# furby_board_v1.net
KiCad netlist of a schematic drawn in EAGLE
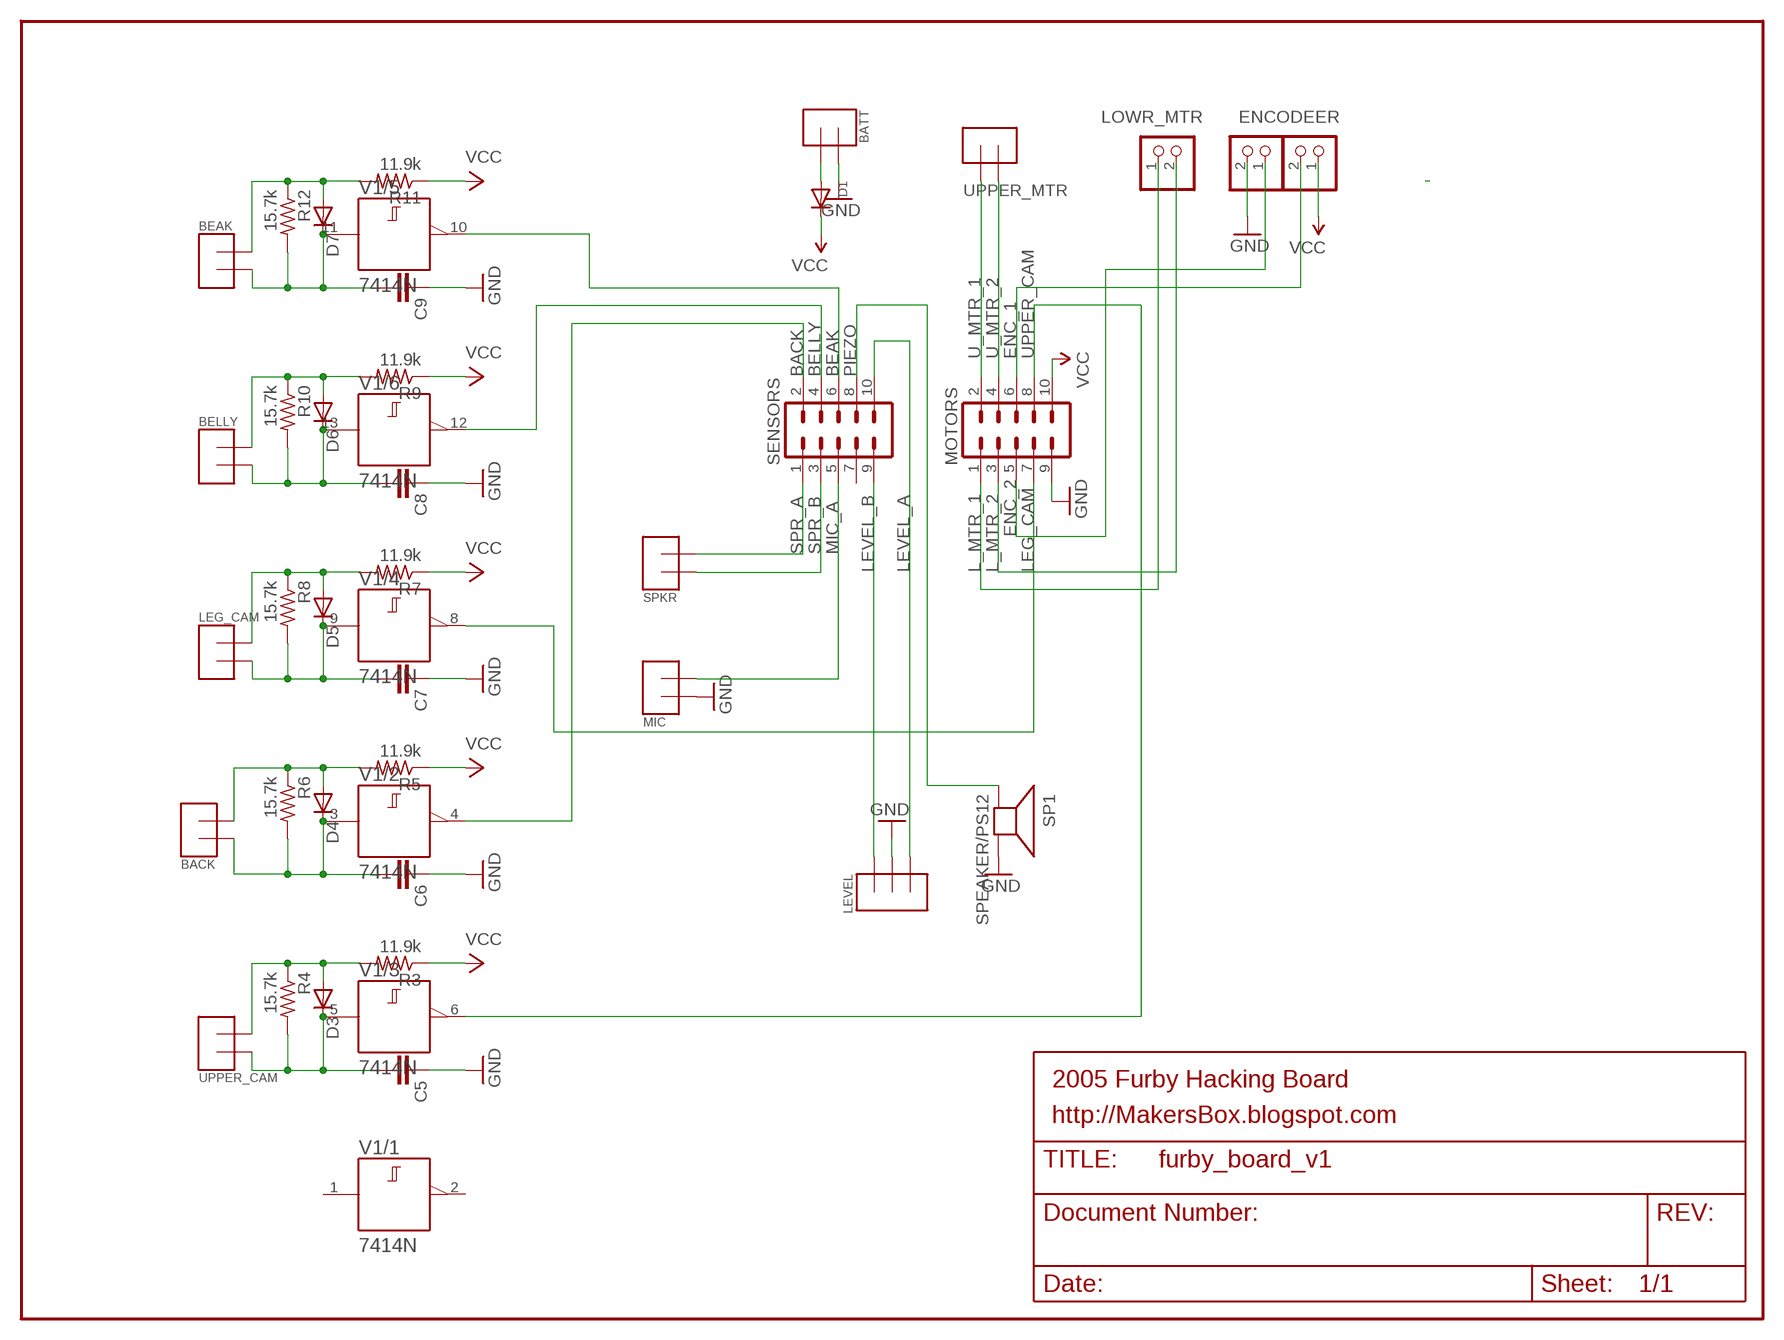
[diagram p0: schematic, sheet 1]

(export (version "E")
  (design (tool "Eeschema 10.0.6"))
  (components
    (comp (ref "BACK")
      (value "TERMINAL2")
      (footprint "eagle-import:TERMINAL_2")
      (libsource (lib "eagle-import") (part "TERMINAL2"))
    )
    (comp (ref "BATT")
      (value "TERMINAL2")
      (footprint "eagle-import:TERMINAL_2")
      (libsource (lib "eagle-import") (part "TERMINAL2"))
    )
    (comp (ref "BEAK")
      (value "TERMINAL2")
      (footprint "eagle-import:TERMINAL_2")
      (libsource (lib "eagle-import") (part "TERMINAL2"))
    )
    (comp (ref "BELLY")
      (value "TERMINAL2")
      (footprint "eagle-import:TERMINAL_2")
      (libsource (lib "eagle-import") (part "TERMINAL2"))
    )
    (comp (ref "C5")
      (value "CAPPTH")
      (footprint "eagle-import:CAP-PTH-SMALL")
      (libsource (lib "eagle-import") (part "CAPPTH"))
    )
    (comp (ref "C6")
      (value "CAPPTH")
      (footprint "eagle-import:CAP-PTH-SMALL")
      (libsource (lib "eagle-import") (part "CAPPTH"))
    )
    (comp (ref "C7")
      (value "CAPPTH")
      (footprint "eagle-import:CAP-PTH-SMALL")
      (libsource (lib "eagle-import") (part "CAPPTH"))
    )
    (comp (ref "C8")
      (value "CAPPTH")
      (footprint "eagle-import:CAP-PTH-SMALL")
      (libsource (lib "eagle-import") (part "CAPPTH"))
    )
    (comp (ref "C9")
      (value "CAPPTH")
      (footprint "eagle-import:CAP-PTH-SMALL")
      (libsource (lib "eagle-import") (part "CAPPTH"))
    )
    (comp (ref "D1")
      (value "DIODEDO-1N4148")
      (footprint "eagle-import:DO-1N4148")
      (libsource (lib "eagle-import") (part "DIODEDO-1N4148"))
    )
    (comp (ref "D3")
      (value "DIODE-D-2.5")
      (footprint "eagle-import:D-2.5")
      (libsource (lib "eagle-import") (part "DIODE-D-2.5"))
    )
    (comp (ref "D4")
      (value "DIODE-D-2.5")
      (footprint "eagle-import:D-2.5")
      (libsource (lib "eagle-import") (part "DIODE-D-2.5"))
    )
    (comp (ref "D5")
      (value "DIODE-D-2.5")
      (footprint "eagle-import:D-2.5")
      (libsource (lib "eagle-import") (part "DIODE-D-2.5"))
    )
    (comp (ref "D6")
      (value "DIODE-D-2.5")
      (footprint "eagle-import:D-2.5")
      (libsource (lib "eagle-import") (part "DIODE-D-2.5"))
    )
    (comp (ref "D7")
      (value "DIODE-D-2.5")
      (footprint "eagle-import:D-2.5")
      (libsource (lib "eagle-import") (part "DIODE-D-2.5"))
    )
    (comp (ref "ENCODE2")
      (value "JST_2PIN-THM")
      (footprint "eagle-import:JST-PH-2-THM")
      (libsource (lib "eagle-import") (part "JST_2PIN-THM"))
    )
    (comp (ref "ENCODEER")
      (value "JST_2PIN-THM")
      (footprint "eagle-import:JST-PH-2-THM")
      (libsource (lib "eagle-import") (part "JST_2PIN-THM"))
    )
    (comp (ref "LEG_CAM")
      (value "TERMINAL2")
      (footprint "eagle-import:TERMINAL_2")
      (libsource (lib "eagle-import") (part "TERMINAL2"))
    )
    (comp (ref "LEVEL")
      (value "TERMINAL")
      (footprint "eagle-import:TERMINAL_3")
      (libsource (lib "eagle-import") (part "TERMINAL"))
    )
    (comp (ref "LOWR_MTR")
      (value "JST_2PIN-THM")
      (footprint "eagle-import:JST-PH-2-THM")
      (libsource (lib "eagle-import") (part "JST_2PIN-THM"))
    )
    (comp (ref "MIC")
      (value "TERMINAL2")
      (footprint "eagle-import:TERMINAL_2")
      (libsource (lib "eagle-import") (part "TERMINAL2"))
    )
    (comp (ref "MOTORS")
      (value "M05X2SHD")
      (footprint "eagle-import:2X5-SHROUDED")
      (libsource (lib "eagle-import") (part "M05X2SHD"))
    )
    (comp (ref "R3")
      (value "11.9k")
      (footprint "eagle-import:0204V")
      (libsource (lib "eagle-import") (part "R-US_0204/2V"))
    )
    (comp (ref "R4")
      (value "15.7k")
      (footprint "eagle-import:0204V")
      (libsource (lib "eagle-import") (part "R-US_0204/2V"))
    )
    (comp (ref "R5")
      (value "11.9k")
      (footprint "eagle-import:0204V")
      (libsource (lib "eagle-import") (part "R-US_0204/2V"))
    )
    (comp (ref "R6")
      (value "15.7k")
      (footprint "eagle-import:0204V")
      (libsource (lib "eagle-import") (part "R-US_0204/2V"))
    )
    (comp (ref "R7")
      (value "11.9k")
      (footprint "eagle-import:0204V")
      (libsource (lib "eagle-import") (part "R-US_0204/2V"))
    )
    (comp (ref "R8")
      (value "15.7k")
      (footprint "eagle-import:0204V")
      (libsource (lib "eagle-import") (part "R-US_0204/2V"))
    )
    (comp (ref "R9")
      (value "11.9k")
      (footprint "eagle-import:0204V")
      (libsource (lib "eagle-import") (part "R-US_0204/2V"))
    )
    (comp (ref "R10")
      (value "15.7k")
      (footprint "eagle-import:0204V")
      (libsource (lib "eagle-import") (part "R-US_0204/2V"))
    )
    (comp (ref "R11")
      (value "11.9k")
      (footprint "eagle-import:0204V")
      (libsource (lib "eagle-import") (part "R-US_0204/2V"))
    )
    (comp (ref "R12")
      (value "15.7k")
      (footprint "eagle-import:0204V")
      (libsource (lib "eagle-import") (part "R-US_0204/2V"))
    )
    (comp (ref "SENSORS")
      (value "M05X2SHD")
      (footprint "eagle-import:2X5-SHROUDED")
      (libsource (lib "eagle-import") (part "M05X2SHD"))
    )
    (comp (ref "SP1")
      (value "SPEAKER/PS12")
      (footprint "eagle-import:PS12")
      (libsource (lib "eagle-import") (part "SPEAKER/PS12"))
    )
    (comp (ref "SPKR")
      (value "TERMINAL2")
      (footprint "eagle-import:TERMINAL_2")
      (libsource (lib "eagle-import") (part "TERMINAL2"))
    )
    (comp (ref "UPPER_CAM")
      (value "TERMINAL2")
      (footprint "eagle-import:TERMINAL_2")
      (libsource (lib "eagle-import") (part "TERMINAL2"))
    )
    (comp (ref "UPPER_MTR")
      (value "TERMINAL2")
      (footprint "eagle-import:TERMINAL_2")
      (libsource (lib "eagle-import") (part "TERMINAL2"))
    )
    (comp (ref "V1")
      (value "7414N")
      (footprint "eagle-import:DIL14")
      (libsource (lib "eagle-import") (part "7414N"))
    )
  )
  (nets
    (net (code "1") (name "/BACK") (class "Default")
      (node (ref "SENSORS") (pin "2") (pinfunction "2_2") (pintype "passive"))
      (node (ref "V1") (pin "4") (pinfunction "Y_4") (pintype "output"))
    )
    (net (code "2") (name "/BEAK") (class "Default")
      (node (ref "SENSORS") (pin "6") (pinfunction "6_6") (pintype "passive"))
      (node (ref "V1") (pin "10") (pinfunction "Y_10") (pintype "output"))
    )
    (net (code "3") (name "/BELLY") (class "Default")
      (node (ref "SENSORS") (pin "4") (pinfunction "4_4") (pintype "passive"))
      (node (ref "V1") (pin "12") (pinfunction "Y_12") (pintype "output"))
    )
    (net (code "4") (name "/ENC_1") (class "Default")
      (node (ref "ENCODE2") (pin "2") (pinfunction "1_2") (pintype "passive"))
      (node (ref "MOTORS") (pin "6") (pinfunction "6_6") (pintype "passive"))
    )
    (net (code "5") (name "/ENC_2") (class "Default")
      (node (ref "ENCODEER") (pin "1") (pinfunction "2_1") (pintype "passive"))
      (node (ref "MOTORS") (pin "5") (pinfunction "5_5") (pintype "passive"))
    )
    (net (code "6") (name "/LEG_CAM") (class "Default")
      (node (ref "MOTORS") (pin "7") (pinfunction "7_7") (pintype "passive"))
      (node (ref "V1") (pin "8") (pinfunction "Y_8") (pintype "output"))
    )
    (net (code "7") (name "/LEVEL_A") (class "Default")
      (node (ref "LEVEL") (pin "P$3") (pinfunction "P$3_P$3") (pintype "bidirectional"))
      (node (ref "SENSORS") (pin "10") (pinfunction "10_10") (pintype "passive"))
    )
    (net (code "8") (name "/LEVEL_B") (class "Default")
      (node (ref "LEVEL") (pin "P$1") (pinfunction "P$1_P$1") (pintype "bidirectional"))
      (node (ref "SENSORS") (pin "9") (pinfunction "9_9") (pintype "passive"))
    )
    (net (code "9") (name "/L_MTR_1") (class "Default")
      (node (ref "LOWR_MTR") (pin "1") (pinfunction "2_1") (pintype "passive"))
      (node (ref "MOTORS") (pin "1") (pinfunction "1_1") (pintype "passive"))
    )
    (net (code "10") (name "/L_MTR_2") (class "Default")
      (node (ref "LOWR_MTR") (pin "2") (pinfunction "1_2") (pintype "passive"))
      (node (ref "MOTORS") (pin "3") (pinfunction "3_3") (pintype "passive"))
    )
    (net (code "11") (name "/MIC_A") (class "Default")
      (node (ref "MIC") (pin "P$2") (pinfunction "P$2_P$2") (pintype "bidirectional"))
      (node (ref "SENSORS") (pin "5") (pinfunction "5_5") (pintype "passive"))
    )
    (net (code "12") (name "/PIEZO") (class "Default")
      (node (ref "SENSORS") (pin "8") (pinfunction "8_8") (pintype "passive"))
      (node (ref "SP1") (pin "P$1") (pinfunction "+_P$1") (pintype "passive"))
    )
    (net (code "13") (name "/SPR_A") (class "Default")
      (node (ref "SENSORS") (pin "1") (pinfunction "1_1") (pintype "passive"))
      (node (ref "SPKR") (pin "P$2") (pinfunction "P$2_P$2") (pintype "bidirectional"))
    )
    (net (code "14") (name "/SPR_B") (class "Default")
      (node (ref "SENSORS") (pin "3") (pinfunction "3_3") (pintype "passive"))
      (node (ref "SPKR") (pin "P$1") (pinfunction "P$1_P$1") (pintype "bidirectional"))
    )
    (net (code "15") (name "/UPPER_CAM") (class "Default")
      (node (ref "MOTORS") (pin "8") (pinfunction "8_8") (pintype "passive"))
      (node (ref "V1") (pin "6") (pinfunction "Y_6") (pintype "output"))
    )
    (net (code "16") (name "/U_MTR_1") (class "Default")
      (node (ref "MOTORS") (pin "2") (pinfunction "2_2") (pintype "passive"))
      (node (ref "UPPER_MTR") (pin "P$1") (pinfunction "P$1_P$1") (pintype "bidirectional"))
    )
    (net (code "17") (name "/U_MTR_2") (class "Default")
      (node (ref "MOTORS") (pin "4") (pinfunction "4_4") (pintype "passive"))
      (node (ref "UPPER_MTR") (pin "P$2") (pinfunction "P$2_P$2") (pintype "bidirectional"))
    )
    (net (code "18") (name "GND") (class "Default")
      (node (ref "BATT") (pin "P$1") (pinfunction "P$1_P$1") (pintype "bidirectional"))
      (node (ref "C5") (pin "1") (pinfunction "1_1") (pintype "passive"))
      (node (ref "C6") (pin "1") (pinfunction "1_1") (pintype "passive"))
      (node (ref "C7") (pin "1") (pinfunction "1_1") (pintype "passive"))
      (node (ref "C8") (pin "1") (pinfunction "1_1") (pintype "passive"))
      (node (ref "C9") (pin "1") (pinfunction "1_1") (pintype "passive"))
      (node (ref "ENCODEER") (pin "2") (pinfunction "1_2") (pintype "passive"))
      (node (ref "LEVEL") (pin "P$2") (pinfunction "P$2_P$2") (pintype "bidirectional"))
      (node (ref "MIC") (pin "P$1") (pinfunction "P$1_P$1") (pintype "bidirectional"))
      (node (ref "MOTORS") (pin "9") (pinfunction "9_9") (pintype "passive"))
      (node (ref "SP1") (pin "P$2") (pinfunction "-_P$2") (pintype "passive"))
    )
    (net (code "19") (name "Net-(BACK-PadP$2)") (class "Default")
      (node (ref "BACK") (pin "P$2") (pinfunction "P$2_P$2") (pintype "bidirectional"))
      (node (ref "D4") (pin "A") (pinfunction "A_A") (pintype "passive"))
      (node (ref "R5") (pin "2") (pinfunction "2_2") (pintype "passive"))
      (node (ref "R6") (pin "1") (pinfunction "1_1") (pintype "passive"))
    )
    (net (code "20") (name "Net-(BATT-PadP$2)") (class "Default")
      (node (ref "BATT") (pin "P$2") (pinfunction "P$2_P$2") (pintype "bidirectional"))
      (node (ref "D1") (pin "A") (pinfunction "A_A") (pintype "passive"))
    )
    (net (code "21") (name "Net-(BEAK-PadP$1)") (class "Default")
      (node (ref "BEAK") (pin "P$1") (pinfunction "P$1_P$1") (pintype "bidirectional"))
      (node (ref "D7") (pin "A") (pinfunction "A_A") (pintype "passive"))
      (node (ref "R11") (pin "2") (pinfunction "2_2") (pintype "passive"))
      (node (ref "R12") (pin "1") (pinfunction "1_1") (pintype "passive"))
    )
    (net (code "22") (name "Net-(BELLY-PadP$1)") (class "Default")
      (node (ref "BELLY") (pin "P$1") (pinfunction "P$1_P$1") (pintype "bidirectional"))
      (node (ref "D6") (pin "A") (pinfunction "A_A") (pintype "passive"))
      (node (ref "R10") (pin "1") (pinfunction "1_1") (pintype "passive"))
      (node (ref "R9") (pin "2") (pinfunction "2_2") (pintype "passive"))
    )
    (net (code "23") (name "Net-(D3-PadA)") (class "Default")
      (node (ref "D3") (pin "A") (pinfunction "A_A") (pintype "passive"))
      (node (ref "R3") (pin "2") (pinfunction "2_2") (pintype "passive"))
      (node (ref "R4") (pin "1") (pinfunction "1_1") (pintype "passive"))
      (node (ref "UPPER_CAM") (pin "P$2") (pinfunction "P$2_P$2") (pintype "bidirectional"))
    )
    (net (code "24") (name "Net-(D5-PadA)") (class "Default")
      (node (ref "D5") (pin "A") (pinfunction "A_A") (pintype "passive"))
      (node (ref "LEG_CAM") (pin "P$1") (pinfunction "P$1_P$1") (pintype "bidirectional"))
      (node (ref "R7") (pin "2") (pinfunction "2_2") (pintype "passive"))
      (node (ref "R8") (pin "1") (pinfunction "1_1") (pintype "passive"))
    )
    (net (code "25") (name "Net-(V1D-A)") (class "Default")
      (node (ref "BACK") (pin "P$1") (pinfunction "P$1_P$1") (pintype "bidirectional"))
      (node (ref "C6") (pin "2") (pinfunction "2_2") (pintype "passive"))
      (node (ref "D4") (pin "C") (pinfunction "C_C") (pintype "passive"))
      (node (ref "R6") (pin "2") (pinfunction "2_2") (pintype "passive"))
      (node (ref "V1") (pin "3") (pinfunction "A_3") (pintype "input"))
    )
    (net (code "26") (name "Net-(V1E-A)") (class "Default")
      (node (ref "C5") (pin "2") (pinfunction "2_2") (pintype "passive"))
      (node (ref "D3") (pin "C") (pinfunction "C_C") (pintype "passive"))
      (node (ref "R4") (pin "2") (pinfunction "2_2") (pintype "passive"))
      (node (ref "UPPER_CAM") (pin "P$1") (pinfunction "P$1_P$1") (pintype "bidirectional"))
      (node (ref "V1") (pin "5") (pinfunction "A_5") (pintype "input"))
    )
    (net (code "27") (name "Net-(V1F-A)") (class "Default")
      (node (ref "C7") (pin "2") (pinfunction "2_2") (pintype "passive"))
      (node (ref "D5") (pin "C") (pinfunction "C_C") (pintype "passive"))
      (node (ref "LEG_CAM") (pin "P$2") (pinfunction "P$2_P$2") (pintype "bidirectional"))
      (node (ref "R8") (pin "2") (pinfunction "2_2") (pintype "passive"))
      (node (ref "V1") (pin "9") (pinfunction "A_9") (pintype "input"))
    )
    (net (code "28") (name "Net-(V1G-A)") (class "Default")
      (node (ref "BEAK") (pin "P$2") (pinfunction "P$2_P$2") (pintype "bidirectional"))
      (node (ref "C9") (pin "2") (pinfunction "2_2") (pintype "passive"))
      (node (ref "D7") (pin "C") (pinfunction "C_C") (pintype "passive"))
      (node (ref "R12") (pin "2") (pinfunction "2_2") (pintype "passive"))
      (node (ref "V1") (pin "11") (pinfunction "A_11") (pintype "input"))
    )
    (net (code "29") (name "Net-(V1H-A)") (class "Default")
      (node (ref "BELLY") (pin "P$2") (pinfunction "P$2_P$2") (pintype "bidirectional"))
      (node (ref "C8") (pin "2") (pinfunction "2_2") (pintype "passive"))
      (node (ref "D6") (pin "C") (pinfunction "C_C") (pintype "passive"))
      (node (ref "R10") (pin "2") (pinfunction "2_2") (pintype "passive"))
      (node (ref "V1") (pin "13") (pinfunction "A_13") (pintype "input"))
    )
    (net (code "30") (name "VCC") (class "Default")
      (node (ref "D1") (pin "C") (pinfunction "C_C") (pintype "passive"))
      (node (ref "ENCODE2") (pin "1") (pinfunction "2_1") (pintype "passive"))
      (node (ref "MOTORS") (pin "10") (pinfunction "10_10") (pintype "passive"))
      (node (ref "R11") (pin "1") (pinfunction "1_1") (pintype "passive"))
      (node (ref "R3") (pin "1") (pinfunction "1_1") (pintype "passive"))
      (node (ref "R5") (pin "1") (pinfunction "1_1") (pintype "passive"))
      (node (ref "R7") (pin "1") (pinfunction "1_1") (pintype "passive"))
      (node (ref "R9") (pin "1") (pinfunction "1_1") (pintype "passive"))
    )
    (net (code "31") (name "unconnected-(SENSORS-Pad7)") (class "Default")
      (node (ref "SENSORS") (pin "7") (pinfunction "7_7") (pintype "passive"))
    )
    (net (code "32") (name "unconnected-(V1C-A-Pad1)") (class "Default")
      (node (ref "V1") (pin "1") (pinfunction "A_1") (pintype "input"))
    )
    (net (code "33") (name "unconnected-(V1C-Y-Pad2)") (class "Default")
      (node (ref "V1") (pin "2") (pinfunction "Y_2") (pintype "output"))
    )
  )
)
